# aq_mx_v1-6-0c.net
KiCad netlist of a schematic drawn in EAGLE
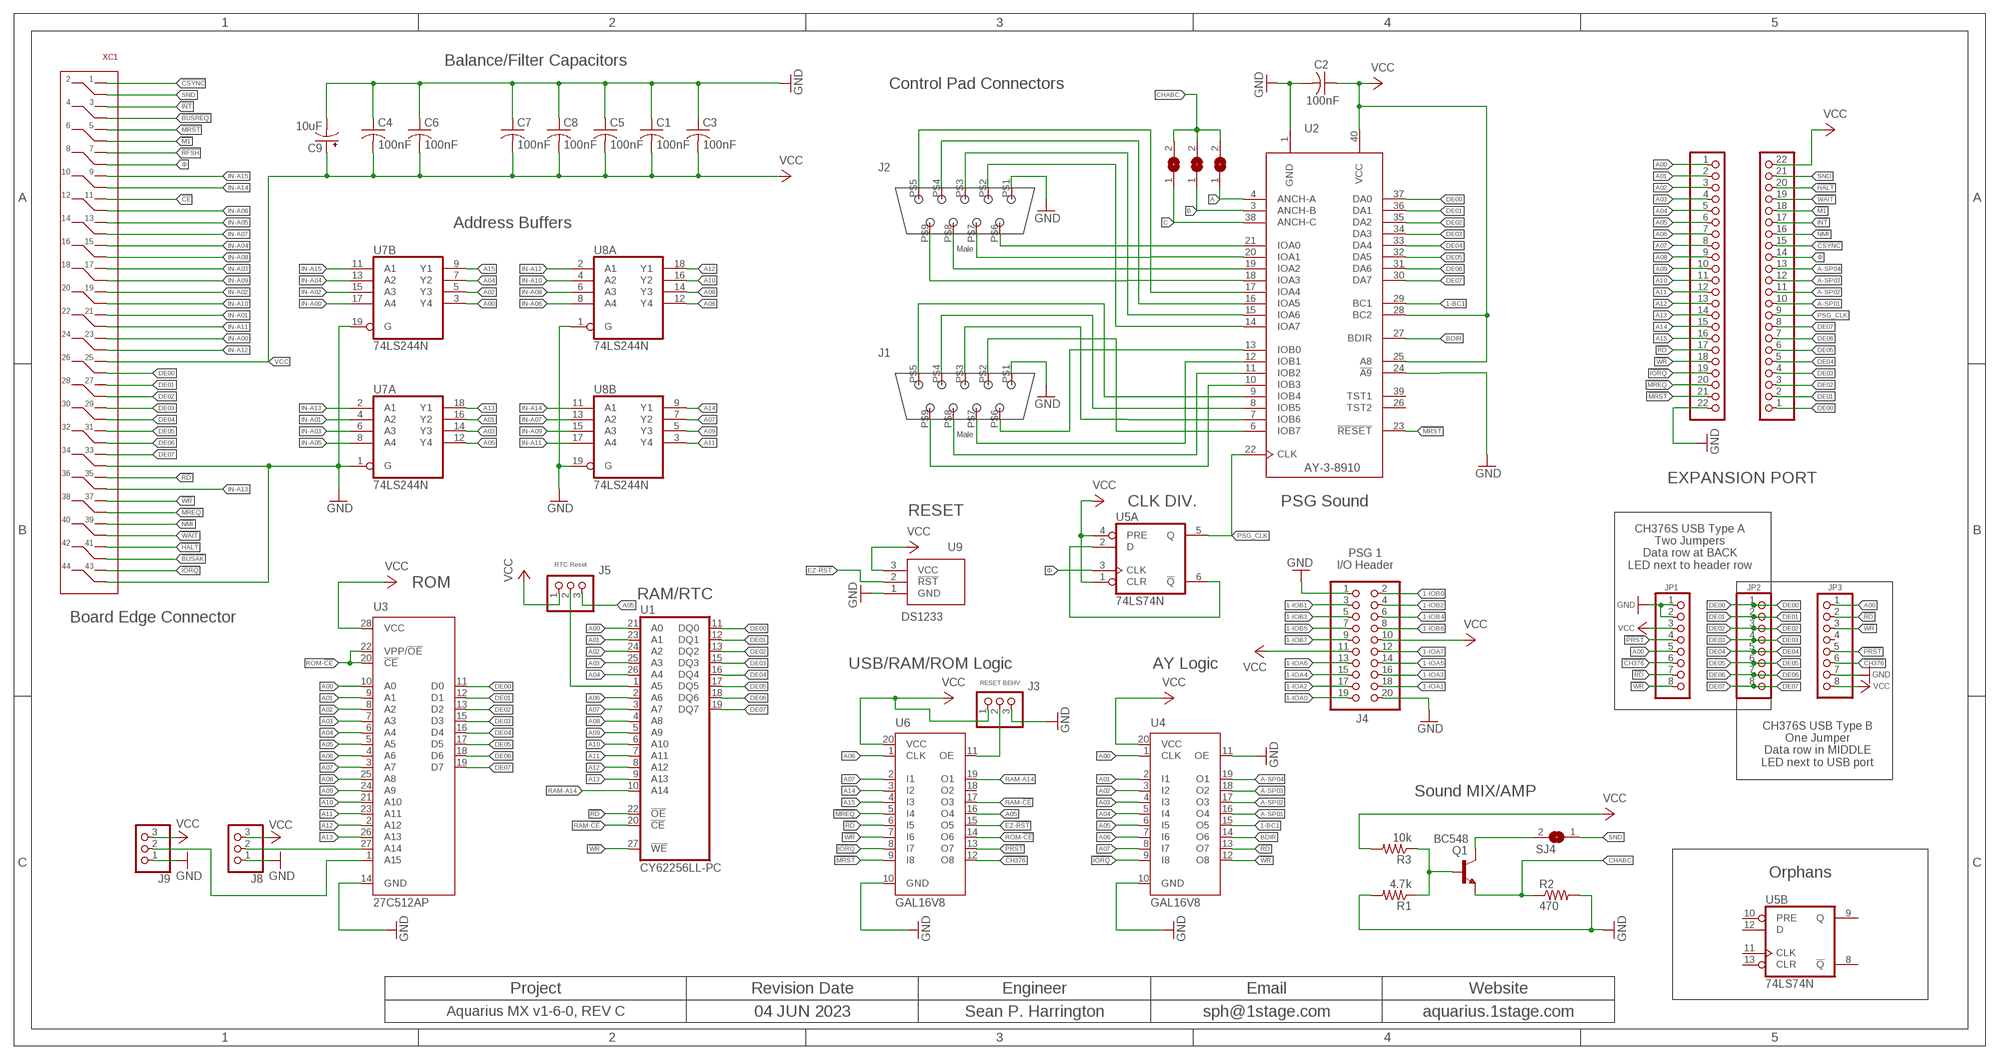
[diagram p0: schematic, sheet 1]

(export (version "E")
  (design (tool "Eeschema 10.0.6"))
  (components
    (comp (ref "C1")
      (value "100nF")
      (footprint "eagle-import:C050-025X075")
      (libsource (lib "eagle-import") (part "C-US050-025X075"))
    )
    (comp (ref "C2")
      (value "100nF")
      (footprint "eagle-import:C050-025X075")
      (libsource (lib "eagle-import") (part "C-US050-025X075"))
    )
    (comp (ref "C3")
      (value "100nF")
      (footprint "eagle-import:C050-025X075")
      (libsource (lib "eagle-import") (part "C-US050-025X075"))
    )
    (comp (ref "C4")
      (value "100nF")
      (footprint "eagle-import:C050-025X075")
      (libsource (lib "eagle-import") (part "C-US050-025X075"))
    )
    (comp (ref "C5")
      (value "100nF")
      (footprint "eagle-import:C050-025X075")
      (libsource (lib "eagle-import") (part "C-US050-025X075"))
    )
    (comp (ref "C6")
      (value "100nF")
      (footprint "eagle-import:C050-025X075")
      (libsource (lib "eagle-import") (part "C-US050-025X075"))
    )
    (comp (ref "C7")
      (value "100nF")
      (footprint "eagle-import:C050-025X075")
      (libsource (lib "eagle-import") (part "C-US050-025X075"))
    )
    (comp (ref "C8")
      (value "100nF")
      (footprint "eagle-import:C050-025X075")
      (libsource (lib "eagle-import") (part "C-US050-025X075"))
    )
    (comp (ref "C9")
      (value "10uF")
      (footprint "eagle-import:E22-6")
      (libsource (lib "eagle-import") (part "CPOL-USE22-6AXIAL"))
    )
    (comp (ref "J1")
      (value "DB9-MALE-RA")
      (footprint "eagle-import:DB9-MALE-RA")
      (libsource (lib "eagle-import") (part "DB9-MALE-RA"))
    )
    (comp (ref "J2")
      (value "DB9-MALE-RA")
      (footprint "eagle-import:DB9-MALE-RA")
      (libsource (lib "eagle-import") (part "DB9-MALE-RA"))
    )
    (comp (ref "J3")
      (value "RESET BEHV.")
      (footprint "eagle-import:1X03")
      (libsource (lib "eagle-import") (part "PINHD-1X3"))
    )
    (comp (ref "J4")
      (value "PINHD-2X10")
      (footprint "eagle-import:2X10")
      (libsource (lib "eagle-import") (part "PINHD-2X10"))
    )
    (comp (ref "J5")
      (value "RTC Reset")
      (footprint "eagle-import:1X03")
      (libsource (lib "eagle-import") (part "PINHD-1X3"))
    )
    (comp (ref "J6")
      (value "PINHD-1X22")
      (footprint "eagle-import:1X22")
      (libsource (lib "eagle-import") (part "PINHD-1X22"))
    )
    (comp (ref "J7")
      (value "PINHD-1X22")
      (footprint "eagle-import:1X22")
      (libsource (lib "eagle-import") (part "PINHD-1X22"))
    )
    (comp (ref "J8")
      (value "PINHD-1X3")
      (footprint "eagle-import:1X03")
      (libsource (lib "eagle-import") (part "PINHD-1X3"))
    )
    (comp (ref "J9")
      (value "PINHD-1X3")
      (footprint "eagle-import:1X03")
      (libsource (lib "eagle-import") (part "PINHD-1X3"))
    )
    (comp (ref "JP1")
      (value "PINHD-1X8")
      (footprint "eagle-import:1X08")
      (libsource (lib "eagle-import") (part "PINHD-1X8"))
    )
    (comp (ref "JP2")
      (value "PINHD-1X8")
      (footprint "eagle-import:1X08")
      (libsource (lib "eagle-import") (part "PINHD-1X8"))
    )
    (comp (ref "JP3")
      (value "PINHD-1X8")
      (footprint "eagle-import:1X08")
      (libsource (lib "eagle-import") (part "PINHD-1X8"))
    )
    (comp (ref "Q1")
      (value "BC548")
      (footprint "eagle-import:TO92-CBE")
      (libsource (lib "eagle-import") (part "-NPN-TO92-CBEBC548"))
    )
    (comp (ref "R1")
      (value "4.7k")
      (footprint "eagle-import:0204_7")
      (libsource (lib "eagle-import") (part "R-US_0204/7"))
    )
    (comp (ref "R2")
      (value "470")
      (footprint "eagle-import:0204_7")
      (libsource (lib "eagle-import") (part "R-US_0204/7"))
    )
    (comp (ref "R3")
      (value "10k")
      (footprint "eagle-import:0204_7")
      (libsource (lib "eagle-import") (part "R-US_0204/7"))
    )
    (comp (ref "SJ1") (value "SJ") (footprint "eagle-import:SJ") (libsource (lib "eagle-import") (part "SJ")))
    (comp (ref "SJ2") (value "SJ") (footprint "eagle-import:SJ") (libsource (lib "eagle-import") (part "SJ")))
    (comp (ref "SJ3") (value "SJ") (footprint "eagle-import:SJ") (libsource (lib "eagle-import") (part "SJ")))
    (comp (ref "SJ4") (value "SJ") (footprint "eagle-import:SJ") (libsource (lib "eagle-import") (part "SJ")))
    (comp (ref "U1")
      (value "CY62256LL-PC")
      (footprint "eagle-import:DIL28-6")
      (libsource (lib "eagle-import") (part "CY62256LL-?PC"))
    )
    (comp (ref "U2")
      (value "AY-3-8910")
      (footprint "eagle-import:RAD38910-DIL40-6")
      (libsource (lib "eagle-import") (part "RAD38910DIL40-6"))
    )
    (comp (ref "U3")
      (value "27C512AP")
      (footprint "eagle-import:DIL28-6")
      (fields (field (name "MPN") "M27C512-90B6"))
      (libsource (lib "eagle-import") (part "27512APC"))
    )
    (comp (ref "U4")
      (value "GAL16V8")
      (footprint "eagle-import:DIL20")
      (fields (field (name "MPN") "ATF16V8CZ-15PU"))
      (libsource (lib "eagle-import") (part "ATF16V8BP3"))
    )
    (comp (ref "U5")
      (value "74LS74N")
      (footprint "eagle-import:DIL14")
      (libsource (lib "eagle-import") (part "7474NLS"))
    )
    (comp (ref "U6")
      (value "GAL16V8")
      (footprint "eagle-import:DIL20")
      (fields (field (name "MPN") "ATF16V8CZ-15PU"))
      (libsource (lib "eagle-import") (part "ATF16V8BP3"))
    )
    (comp (ref "U7")
      (value "74LS244N")
      (footprint "eagle-import:DIL20")
      (libsource (lib "eagle-import") (part "74244NLS"))
    )
    (comp (ref "U8")
      (value "74LS244N")
      (footprint "eagle-import:DIL20")
      (libsource (lib "eagle-import") (part "74244NLS"))
    )
    (comp (ref "U9")
      (value "DS1233")
      (footprint "eagle-import:TO-92")
      (fields
        (field (name "ARROW_PART_NUMBER") "DS1233-10+")
        (field (name "MOUSER_PART_NUMBER") "700-DS1233-10")
      )
      (libsource (lib "eagle-import") (part "DS1233-10+"))
    )
    (comp (ref "XC1")
      (value "AQ-CART-EDGE")
      (footprint "eagle-import:AQ-CART-EDGE")
      (libsource (lib "eagle-import") (part "AQ-CART-EDGE"))
    )
  )
  (nets
    (net (code "1") (name "/EZ-~{RST}") (class "Default")
      (node (ref "U6") (pin "15") (pinfunction "O5_15") (pintype "output"))
      (node (ref "U9") (pin "2") (pinfunction "~{RST}_2") (pintype "input"))
    )
    (net (code "2") (name "/RAM-~{CE}") (class "Default")
      (node (ref "U1") (pin "20") (pinfunction "~{CE}_20") (pintype "input"))
      (node (ref "U6") (pin "17") (pinfunction "O3_17") (pintype "output"))
    )
    (net (code "3") (name "/ROM-~{CE}") (class "Default")
      (node (ref "U3") (pin "20") (pinfunction "~{CE}_20") (pintype "input"))
      (node (ref "U3") (pin "22") (pinfunction "VPP/~{OE}_22") (pintype "input"))
      (node (ref "U6") (pin "14") (pinfunction "O6_14") (pintype "output"))
    )
    (net (code "4") (name "/~{BUSAK}") (class "Default")
      (node (ref "XC1") (pin "P$42") (pinfunction "X42_P$42") (pintype "bidirectional"))
    )
    (net (code "5") (name "/~{BUSREQ}") (class "Default")
      (node (ref "XC1") (pin "P$4") (pinfunction "X4_P$4") (pintype "bidirectional"))
    )
    (net (code "6") (name "/~{CE}") (class "Default")
      (node (ref "XC1") (pin "P$11") (pinfunction "X11_P$11") (pintype "bidirectional"))
    )
    (net (code "7") (name "/~{CH376}") (class "Default")
      (node (ref "JP1") (pin "6") (pinfunction "6_6") (pintype "passive"))
      (node (ref "JP3") (pin "6") (pinfunction "6_6") (pintype "passive"))
      (node (ref "U6") (pin "12") (pinfunction "O8_12") (pintype "output"))
    )
    (net (code "8") (name "/~{CSYNC}") (class "Default")
      (node (ref "J6") (pin "15") (pinfunction "15_15") (pintype "passive"))
      (node (ref "XC1") (pin "P$1") (pinfunction "X1_P$1") (pintype "bidirectional"))
    )
    (net (code "9") (name "/~{HALT}") (class "Default")
      (node (ref "J6") (pin "20") (pinfunction "20_20") (pintype "passive"))
      (node (ref "XC1") (pin "P$41") (pinfunction "X41_P$41") (pintype "bidirectional"))
    )
    (net (code "10") (name "/~{INT}") (class "Default")
      (node (ref "J6") (pin "17") (pinfunction "17_17") (pintype "passive"))
      (node (ref "XC1") (pin "P$3") (pinfunction "X3_P$3") (pintype "bidirectional"))
    )
    (net (code "11") (name "/~{IORQ}") (class "Default")
      (node (ref "J7") (pin "19") (pinfunction "19_19") (pintype "passive"))
      (node (ref "U4") (pin "9") (pinfunction "I8_9") (pintype "input"))
      (node (ref "U6") (pin "8") (pinfunction "I7_8") (pintype "input"))
      (node (ref "XC1") (pin "P$43") (pinfunction "X43_P$43") (pintype "bidirectional"))
    )
    (net (code "12") (name "/~{M1}") (class "Default")
      (node (ref "J6") (pin "18") (pinfunction "18_18") (pintype "passive"))
      (node (ref "XC1") (pin "P$6") (pinfunction "X6_P$6") (pintype "bidirectional"))
    )
    (net (code "13") (name "/~{MREQ}") (class "Default")
      (node (ref "J7") (pin "20") (pinfunction "20_20") (pintype "passive"))
      (node (ref "U6") (pin "5") (pinfunction "I4_5") (pintype "input"))
      (node (ref "XC1") (pin "P$38") (pinfunction "X38_P$38") (pintype "bidirectional"))
    )
    (net (code "14") (name "/~{MRST}") (class "Default")
      (node (ref "J7") (pin "21") (pinfunction "21_21") (pintype "passive"))
      (node (ref "U2") (pin "23") (pinfunction "~{RESET}_23") (pintype "bidirectional"))
      (node (ref "U6") (pin "9") (pinfunction "I8_9") (pintype "input"))
      (node (ref "XC1") (pin "P$5") (pinfunction "X5_P$5") (pintype "bidirectional"))
    )
    (net (code "15") (name "/~{NMI}") (class "Default")
      (node (ref "J6") (pin "16") (pinfunction "16_16") (pintype "passive"))
      (node (ref "XC1") (pin "P$39") (pinfunction "X39_P$39") (pintype "bidirectional"))
    )
    (net (code "16") (name "/~{PRST}") (class "Default")
      (node (ref "JP1") (pin "4") (pinfunction "4_4") (pintype "passive"))
      (node (ref "JP3") (pin "5") (pinfunction "5_5") (pintype "passive"))
      (node (ref "U6") (pin "13") (pinfunction "O7_13") (pintype "output"))
    )
    (net (code "17") (name "/~{RD}") (class "Default")
      (node (ref "J7") (pin "17") (pinfunction "17_17") (pintype "passive"))
      (node (ref "JP1") (pin "7") (pinfunction "7_7") (pintype "passive"))
      (node (ref "JP3") (pin "2") (pinfunction "2_2") (pintype "passive"))
      (node (ref "U1") (pin "22") (pinfunction "~{OE}_22") (pintype "input"))
      (node (ref "U4") (pin "13") (pinfunction "O7_13") (pintype "output"))
      (node (ref "U6") (pin "6") (pinfunction "I5_6") (pintype "input"))
      (node (ref "XC1") (pin "P$35") (pinfunction "X35_P$35") (pintype "bidirectional"))
    )
    (net (code "18") (name "/~{RFSH}") (class "Default")
      (node (ref "XC1") (pin "P$7") (pinfunction "X7_P$7") (pintype "bidirectional"))
    )
    (net (code "19") (name "/~{WAIT}") (class "Default")
      (node (ref "J6") (pin "19") (pinfunction "19_19") (pintype "passive"))
      (node (ref "XC1") (pin "P$40") (pinfunction "X40_P$40") (pintype "bidirectional"))
    )
    (net (code "20") (name "/~{WR}") (class "Default")
      (node (ref "J7") (pin "18") (pinfunction "18_18") (pintype "passive"))
      (node (ref "JP1") (pin "8") (pinfunction "8_8") (pintype "passive"))
      (node (ref "JP3") (pin "3") (pinfunction "3_3") (pintype "passive"))
      (node (ref "U1") (pin "27") (pinfunction "~{WE}_27") (pintype "input"))
      (node (ref "U4") (pin "12") (pinfunction "O8_12") (pintype "output"))
      (node (ref "U6") (pin "7") (pinfunction "I6_7") (pintype "input"))
      (node (ref "XC1") (pin "P$37") (pinfunction "X37_P$37") (pintype "bidirectional"))
    )
    (net (code "21") (name "1-BC1") (class "Default")
      (node (ref "U2") (pin "29") (pinfunction "BC1_29") (pintype "bidirectional"))
      (node (ref "U4") (pin "15") (pinfunction "O5_15") (pintype "output"))
    )
    (net (code "22") (name "1-IOA0") (class "Default")
      (node (ref "J2") (pin "P$6") (pinfunction "P$6_P$6") (pintype "bidirectional"))
      (node (ref "J4") (pin "19") (pinfunction "19_19") (pintype "passive"))
      (node (ref "U2") (pin "21") (pinfunction "IOA0_21") (pintype "bidirectional"))
    )
    (net (code "23") (name "1-IOA1") (class "Default")
      (node (ref "J2") (pin "P$7") (pinfunction "P$7_P$7") (pintype "bidirectional"))
      (node (ref "J4") (pin "18") (pinfunction "18_18") (pintype "passive"))
      (node (ref "U2") (pin "20") (pinfunction "IOA1_20") (pintype "bidirectional"))
    )
    (net (code "24") (name "1-IOA2") (class "Default")
      (node (ref "J2") (pin "P$8") (pinfunction "P$8_P$8") (pintype "bidirectional"))
      (node (ref "J4") (pin "17") (pinfunction "17_17") (pintype "passive"))
      (node (ref "U2") (pin "19") (pinfunction "IOA2_19") (pintype "bidirectional"))
    )
    (net (code "25") (name "1-IOA3") (class "Default")
      (node (ref "J2") (pin "P$9") (pinfunction "P$9_P$9") (pintype "bidirectional"))
      (node (ref "J4") (pin "16") (pinfunction "16_16") (pintype "passive"))
      (node (ref "U2") (pin "18") (pinfunction "IOA3_18") (pintype "bidirectional"))
    )
    (net (code "26") (name "1-IOA4") (class "Default")
      (node (ref "J2") (pin "P$5") (pinfunction "P$5_P$5") (pintype "bidirectional"))
      (node (ref "J4") (pin "15") (pinfunction "15_15") (pintype "passive"))
      (node (ref "U2") (pin "17") (pinfunction "IOA4_17") (pintype "bidirectional"))
    )
    (net (code "27") (name "1-IOA5") (class "Default")
      (node (ref "J2") (pin "P$4") (pinfunction "P$4_P$4") (pintype "bidirectional"))
      (node (ref "J4") (pin "14") (pinfunction "14_14") (pintype "passive"))
      (node (ref "U2") (pin "16") (pinfunction "IOA5_16") (pintype "bidirectional"))
    )
    (net (code "28") (name "1-IOA6") (class "Default")
      (node (ref "J2") (pin "P$3") (pinfunction "P$3_P$3") (pintype "bidirectional"))
      (node (ref "J4") (pin "13") (pinfunction "13_13") (pintype "passive"))
      (node (ref "U2") (pin "15") (pinfunction "IOA6_15") (pintype "bidirectional"))
    )
    (net (code "29") (name "1-IOA7") (class "Default")
      (node (ref "J2") (pin "P$2") (pinfunction "P$2_P$2") (pintype "bidirectional"))
      (node (ref "J4") (pin "12") (pinfunction "12_12") (pintype "passive"))
      (node (ref "U2") (pin "14") (pinfunction "IOA7_14") (pintype "bidirectional"))
    )
    (net (code "30") (name "1-IOB0") (class "Default")
      (node (ref "J1") (pin "P$6") (pinfunction "P$6_P$6") (pintype "bidirectional"))
      (node (ref "J4") (pin "2") (pinfunction "2_2") (pintype "passive"))
      (node (ref "U2") (pin "13") (pinfunction "IOB0_13") (pintype "bidirectional"))
    )
    (net (code "31") (name "1-IOB1") (class "Default")
      (node (ref "J1") (pin "P$7") (pinfunction "P$7_P$7") (pintype "bidirectional"))
      (node (ref "J4") (pin "3") (pinfunction "3_3") (pintype "passive"))
      (node (ref "U2") (pin "12") (pinfunction "IOB1_12") (pintype "bidirectional"))
    )
    (net (code "32") (name "1-IOB2") (class "Default")
      (node (ref "J1") (pin "P$8") (pinfunction "P$8_P$8") (pintype "bidirectional"))
      (node (ref "J4") (pin "4") (pinfunction "4_4") (pintype "passive"))
      (node (ref "U2") (pin "11") (pinfunction "IOB2_11") (pintype "bidirectional"))
    )
    (net (code "33") (name "1-IOB3") (class "Default")
      (node (ref "J1") (pin "P$9") (pinfunction "P$9_P$9") (pintype "bidirectional"))
      (node (ref "J4") (pin "5") (pinfunction "5_5") (pintype "passive"))
      (node (ref "U2") (pin "10") (pinfunction "IOB3_10") (pintype "bidirectional"))
    )
    (net (code "34") (name "1-IOB4") (class "Default")
      (node (ref "J1") (pin "P$5") (pinfunction "P$5_P$5") (pintype "bidirectional"))
      (node (ref "J4") (pin "6") (pinfunction "6_6") (pintype "passive"))
      (node (ref "U2") (pin "9") (pinfunction "IOB4_9") (pintype "bidirectional"))
    )
    (net (code "35") (name "1-IOB5") (class "Default")
      (node (ref "J1") (pin "P$4") (pinfunction "P$4_P$4") (pintype "bidirectional"))
      (node (ref "J4") (pin "7") (pinfunction "7_7") (pintype "passive"))
      (node (ref "U2") (pin "8") (pinfunction "IOB5_8") (pintype "bidirectional"))
    )
    (net (code "36") (name "1-IOB6") (class "Default")
      (node (ref "J1") (pin "P$3") (pinfunction "P$3_P$3") (pintype "bidirectional"))
      (node (ref "J4") (pin "8") (pinfunction "8_8") (pintype "passive"))
      (node (ref "U2") (pin "7") (pinfunction "IOB6_7") (pintype "bidirectional"))
    )
    (net (code "37") (name "1-IOB7") (class "Default")
      (node (ref "J1") (pin "P$2") (pinfunction "P$2_P$2") (pintype "bidirectional"))
      (node (ref "J4") (pin "9") (pinfunction "9_9") (pintype "passive"))
      (node (ref "U2") (pin "6") (pinfunction "IOB7_6") (pintype "bidirectional"))
    )
    (net (code "38") (name "A") (class "Default")
      (node (ref "SJ1") (pin "1") (pinfunction "1_1") (pintype "passive"))
      (node (ref "U2") (pin "4") (pinfunction "ANCH-A_4") (pintype "bidirectional"))
    )
    (net (code "39") (name "A-SP01") (class "Default")
      (node (ref "J6") (pin "10") (pinfunction "10_10") (pintype "passive"))
      (node (ref "U4") (pin "16") (pinfunction "O4_16") (pintype "output"))
    )
    (net (code "40") (name "A-SP02") (class "Default")
      (node (ref "J6") (pin "11") (pinfunction "11_11") (pintype "passive"))
      (node (ref "U4") (pin "17") (pinfunction "O3_17") (pintype "output"))
    )
    (net (code "41") (name "A-SP03") (class "Default")
      (node (ref "J6") (pin "12") (pinfunction "12_12") (pintype "passive"))
      (node (ref "U4") (pin "18") (pinfunction "O2_18") (pintype "output"))
    )
    (net (code "42") (name "A-SP04") (class "Default")
      (node (ref "J6") (pin "13") (pinfunction "13_13") (pintype "passive"))
      (node (ref "U4") (pin "19") (pinfunction "O1_19") (pintype "output"))
    )
    (net (code "43") (name "A00") (class "Default")
      (node (ref "J7") (pin "1") (pinfunction "1_1") (pintype "passive"))
      (node (ref "JP1") (pin "5") (pinfunction "5_5") (pintype "passive"))
      (node (ref "JP3") (pin "1") (pinfunction "1_1") (pintype "passive"))
      (node (ref "U1") (pin "21") (pinfunction "A0_21") (pintype "input"))
      (node (ref "U3") (pin "10") (pinfunction "A0_10") (pintype "input"))
      (node (ref "U4") (pin "1") (pinfunction "CLK_1") (pintype "input"))
      (node (ref "U7") (pin "3") (pinfunction "Y4_3") (pintype "tri_state"))
    )
    (net (code "44") (name "A01") (class "Default")
      (node (ref "J7") (pin "2") (pinfunction "2_2") (pintype "passive"))
      (node (ref "U1") (pin "23") (pinfunction "A1_23") (pintype "input"))
      (node (ref "U3") (pin "9") (pinfunction "A1_9") (pintype "input"))
      (node (ref "U4") (pin "2") (pinfunction "I1_2") (pintype "input"))
      (node (ref "U7") (pin "16") (pinfunction "Y2_16") (pintype "tri_state"))
    )
    (net (code "45") (name "A02") (class "Default")
      (node (ref "J7") (pin "3") (pinfunction "3_3") (pintype "passive"))
      (node (ref "U1") (pin "24") (pinfunction "A2_24") (pintype "input"))
      (node (ref "U3") (pin "8") (pinfunction "A2_8") (pintype "input"))
      (node (ref "U4") (pin "3") (pinfunction "I2_3") (pintype "input"))
      (node (ref "U7") (pin "5") (pinfunction "Y3_5") (pintype "tri_state"))
    )
    (net (code "46") (name "A03") (class "Default")
      (node (ref "J7") (pin "4") (pinfunction "4_4") (pintype "passive"))
      (node (ref "U1") (pin "25") (pinfunction "A3_25") (pintype "input"))
      (node (ref "U3") (pin "7") (pinfunction "A3_7") (pintype "input"))
      (node (ref "U4") (pin "4") (pinfunction "I3_4") (pintype "input"))
      (node (ref "U7") (pin "14") (pinfunction "Y3_14") (pintype "tri_state"))
    )
    (net (code "47") (name "A04") (class "Default")
      (node (ref "J7") (pin "5") (pinfunction "5_5") (pintype "passive"))
      (node (ref "U1") (pin "26") (pinfunction "A4_26") (pintype "input"))
      (node (ref "U3") (pin "6") (pinfunction "A4_6") (pintype "input"))
      (node (ref "U4") (pin "5") (pinfunction "I4_5") (pintype "input"))
      (node (ref "U7") (pin "7") (pinfunction "Y2_7") (pintype "tri_state"))
    )
    (net (code "48") (name "A05") (class "Default")
      (node (ref "J5") (pin "3") (pinfunction "3_3") (pintype "passive"))
      (node (ref "J7") (pin "6") (pinfunction "6_6") (pintype "passive"))
      (node (ref "U3") (pin "5") (pinfunction "A5_5") (pintype "input"))
      (node (ref "U4") (pin "6") (pinfunction "I5_6") (pintype "input"))
      (node (ref "U6") (pin "16") (pinfunction "O4_16") (pintype "output"))
      (node (ref "U7") (pin "12") (pinfunction "Y4_12") (pintype "tri_state"))
    )
    (net (code "49") (name "A06") (class "Default")
      (node (ref "J7") (pin "7") (pinfunction "7_7") (pintype "passive"))
      (node (ref "U1") (pin "2") (pinfunction "A6_2") (pintype "input"))
      (node (ref "U3") (pin "4") (pinfunction "A6_4") (pintype "input"))
      (node (ref "U4") (pin "7") (pinfunction "I6_7") (pintype "input"))
      (node (ref "U6") (pin "1") (pinfunction "CLK_1") (pintype "input"))
      (node (ref "U8") (pin "12") (pinfunction "Y4_12") (pintype "tri_state"))
    )
    (net (code "50") (name "A07") (class "Default")
      (node (ref "J7") (pin "8") (pinfunction "8_8") (pintype "passive"))
      (node (ref "U1") (pin "3") (pinfunction "A7_3") (pintype "input"))
      (node (ref "U3") (pin "3") (pinfunction "A7_3") (pintype "input"))
      (node (ref "U4") (pin "8") (pinfunction "I7_8") (pintype "input"))
      (node (ref "U6") (pin "2") (pinfunction "I1_2") (pintype "input"))
      (node (ref "U8") (pin "7") (pinfunction "Y2_7") (pintype "tri_state"))
    )
    (net (code "51") (name "A08") (class "Default")
      (node (ref "J7") (pin "9") (pinfunction "9_9") (pintype "passive"))
      (node (ref "U1") (pin "4") (pinfunction "A8_4") (pintype "input"))
      (node (ref "U3") (pin "25") (pinfunction "A8_25") (pintype "input"))
      (node (ref "U8") (pin "14") (pinfunction "Y3_14") (pintype "tri_state"))
    )
    (net (code "52") (name "A09") (class "Default")
      (node (ref "J7") (pin "10") (pinfunction "10_10") (pintype "passive"))
      (node (ref "U1") (pin "5") (pinfunction "A9_5") (pintype "input"))
      (node (ref "U3") (pin "24") (pinfunction "A9_24") (pintype "input"))
      (node (ref "U8") (pin "5") (pinfunction "Y3_5") (pintype "tri_state"))
    )
    (net (code "53") (name "A10") (class "Default")
      (node (ref "J7") (pin "11") (pinfunction "11_11") (pintype "passive"))
      (node (ref "U1") (pin "6") (pinfunction "A10_6") (pintype "input"))
      (node (ref "U3") (pin "21") (pinfunction "A10_21") (pintype "input"))
      (node (ref "U8") (pin "16") (pinfunction "Y2_16") (pintype "tri_state"))
    )
    (net (code "54") (name "A11") (class "Default")
      (node (ref "J7") (pin "12") (pinfunction "12_12") (pintype "passive"))
      (node (ref "U1") (pin "7") (pinfunction "A11_7") (pintype "input"))
      (node (ref "U3") (pin "23") (pinfunction "A11_23") (pintype "input"))
      (node (ref "U8") (pin "3") (pinfunction "Y4_3") (pintype "tri_state"))
    )
    (net (code "55") (name "A12") (class "Default")
      (node (ref "J7") (pin "13") (pinfunction "13_13") (pintype "passive"))
      (node (ref "U1") (pin "8") (pinfunction "A12_8") (pintype "input"))
      (node (ref "U3") (pin "2") (pinfunction "A12_2") (pintype "input"))
      (node (ref "U8") (pin "18") (pinfunction "Y1_18") (pintype "tri_state"))
    )
    (net (code "56") (name "A13") (class "Default")
      (node (ref "J7") (pin "14") (pinfunction "14_14") (pintype "passive"))
      (node (ref "U1") (pin "9") (pinfunction "A13_9") (pintype "input"))
      (node (ref "U3") (pin "26") (pinfunction "A13_26") (pintype "input"))
      (node (ref "U7") (pin "18") (pinfunction "Y1_18") (pintype "tri_state"))
    )
    (net (code "57") (name "A14") (class "Default")
      (node (ref "J7") (pin "15") (pinfunction "15_15") (pintype "passive"))
      (node (ref "U6") (pin "3") (pinfunction "I2_3") (pintype "input"))
      (node (ref "U8") (pin "9") (pinfunction "Y1_9") (pintype "tri_state"))
    )
    (net (code "58") (name "A15") (class "Default")
      (node (ref "J7") (pin "16") (pinfunction "16_16") (pintype "passive"))
      (node (ref "U6") (pin "4") (pinfunction "I3_4") (pintype "input"))
      (node (ref "U7") (pin "9") (pinfunction "Y1_9") (pintype "tri_state"))
    )
    (net (code "59") (name "B") (class "Default")
      (node (ref "SJ2") (pin "1") (pinfunction "1_1") (pintype "passive"))
      (node (ref "U2") (pin "3") (pinfunction "ANCH-B_3") (pintype "bidirectional"))
    )
    (net (code "60") (name "BDIR") (class "Default")
      (node (ref "U2") (pin "27") (pinfunction "BDIR_27") (pintype "bidirectional"))
      (node (ref "U4") (pin "14") (pinfunction "O6_14") (pintype "output"))
    )
    (net (code "61") (name "C") (class "Default")
      (node (ref "SJ3") (pin "1") (pinfunction "1_1") (pintype "passive"))
      (node (ref "U2") (pin "38") (pinfunction "ANCH-C_38") (pintype "bidirectional"))
    )
    (net (code "62") (name "CHABC") (class "Default")
      (node (ref "Q1") (pin "E") (pinfunction "E_E") (pintype "passive"))
      (node (ref "R2") (pin "1") (pinfunction "1_1") (pintype "passive"))
      (node (ref "SJ1") (pin "2") (pinfunction "2_2") (pintype "passive"))
      (node (ref "SJ2") (pin "2") (pinfunction "2_2") (pintype "passive"))
      (node (ref "SJ3") (pin "2") (pinfunction "2_2") (pintype "passive"))
    )
    (net (code "63") (name "DE00") (class "Default")
      (node (ref "J6") (pin "1") (pinfunction "1_1") (pintype "passive"))
      (node (ref "JP2") (pin "1") (pinfunction "1_1") (pintype "passive"))
      (node (ref "U1") (pin "11") (pinfunction "DQ0_11") (pintype "bidirectional"))
      (node (ref "U2") (pin "37") (pinfunction "DA0_37") (pintype "bidirectional"))
      (node (ref "U3") (pin "11") (pinfunction "D0_11") (pintype "tri_state"))
      (node (ref "XC1") (pin "P$26") (pinfunction "X26_P$26") (pintype "bidirectional"))
    )
    (net (code "64") (name "DE01") (class "Default")
      (node (ref "J6") (pin "2") (pinfunction "2_2") (pintype "passive"))
      (node (ref "JP2") (pin "2") (pinfunction "2_2") (pintype "passive"))
      (node (ref "U1") (pin "12") (pinfunction "DQ1_12") (pintype "bidirectional"))
      (node (ref "U2") (pin "36") (pinfunction "DA1_36") (pintype "bidirectional"))
      (node (ref "U3") (pin "12") (pinfunction "D1_12") (pintype "tri_state"))
      (node (ref "XC1") (pin "P$27") (pinfunction "X27_P$27") (pintype "bidirectional"))
    )
    (net (code "65") (name "DE02") (class "Default")
      (node (ref "J6") (pin "3") (pinfunction "3_3") (pintype "passive"))
      (node (ref "JP2") (pin "3") (pinfunction "3_3") (pintype "passive"))
      (node (ref "U1") (pin "13") (pinfunction "DQ2_13") (pintype "bidirectional"))
      (node (ref "U2") (pin "35") (pinfunction "DA2_35") (pintype "bidirectional"))
      (node (ref "U3") (pin "13") (pinfunction "D2_13") (pintype "tri_state"))
      (node (ref "XC1") (pin "P$28") (pinfunction "X28_P$28") (pintype "bidirectional"))
    )
    (net (code "66") (name "DE03") (class "Default")
      (node (ref "J6") (pin "4") (pinfunction "4_4") (pintype "passive"))
      (node (ref "JP2") (pin "4") (pinfunction "4_4") (pintype "passive"))
      (node (ref "U1") (pin "15") (pinfunction "DQ3_15") (pintype "bidirectional"))
      (node (ref "U2") (pin "34") (pinfunction "DA3_34") (pintype "bidirectional"))
      (node (ref "U3") (pin "15") (pinfunction "D3_15") (pintype "tri_state"))
      (node (ref "XC1") (pin "P$29") (pinfunction "X29_P$29") (pintype "bidirectional"))
    )
    (net (code "67") (name "DE04") (class "Default")
      (node (ref "J6") (pin "5") (pinfunction "5_5") (pintype "passive"))
      (node (ref "JP2") (pin "5") (pinfunction "5_5") (pintype "passive"))
      (node (ref "U1") (pin "16") (pinfunction "DQ4_16") (pintype "bidirectional"))
      (node (ref "U2") (pin "33") (pinfunction "DA4_33") (pintype "bidirectional"))
      (node (ref "U3") (pin "16") (pinfunction "D4_16") (pintype "tri_state"))
      (node (ref "XC1") (pin "P$30") (pinfunction "X30_P$30") (pintype "bidirectional"))
    )
    (net (code "68") (name "DE05") (class "Default")
      (node (ref "J6") (pin "6") (pinfunction "6_6") (pintype "passive"))
      (node (ref "JP2") (pin "6") (pinfunction "6_6") (pintype "passive"))
      (node (ref "U1") (pin "17") (pinfunction "DQ5_17") (pintype "bidirectional"))
      (node (ref "U2") (pin "32") (pinfunction "DA5_32") (pintype "bidirectional"))
      (node (ref "U3") (pin "17") (pinfunction "D5_17") (pintype "tri_state"))
      (node (ref "XC1") (pin "P$31") (pinfunction "X31_P$31") (pintype "bidirectional"))
    )
    (net (code "69") (name "DE06") (class "Default")
      (node (ref "J6") (pin "7") (pinfunction "7_7") (pintype "passive"))
      (node (ref "JP2") (pin "7") (pinfunction "7_7") (pintype "passive"))
      (node (ref "U1") (pin "18") (pinfunction "DQ6_18") (pintype "bidirectional"))
      (node (ref "U2") (pin "31") (pinfunction "DA6_31") (pintype "bidirectional"))
      (node (ref "U3") (pin "18") (pinfunction "D6_18") (pintype "tri_state"))
      (node (ref "XC1") (pin "P$32") (pinfunction "X32_P$32") (pintype "bidirectional"))
    )
    (net (code "70") (name "DE07") (class "Default")
      (node (ref "J6") (pin "8") (pinfunction "8_8") (pintype "passive"))
      (node (ref "JP2") (pin "8") (pinfunction "8_8") (pintype "passive"))
      (node (ref "U1") (pin "19") (pinfunction "DQ7_19") (pintype "bidirectional"))
      (node (ref "U2") (pin "30") (pinfunction "DA7_30") (pintype "bidirectional"))
      (node (ref "U3") (pin "19") (pinfunction "D7_19") (pintype "tri_state"))
      (node (ref "XC1") (pin "P$33") (pinfunction "X33_P$33") (pintype "bidirectional"))
    )
    (net (code "71") (name "GND") (class "Default")
      (node (ref "C1") (pin "1") (pinfunction "1_1") (pintype "passive"))
      (node (ref "C2") (pin "2") (pinfunction "2_2") (pintype "passive"))
      (node (ref "C3") (pin "1") (pinfunction "1_1") (pintype "passive"))
      (node (ref "C4") (pin "1") (pinfunction "1_1") (pintype "passive"))
      (node (ref "C5") (pin "1") (pinfunction "1_1") (pintype "passive"))
      (node (ref "C6") (pin "1") (pinfunction "1_1") (pintype "passive"))
      (node (ref "C7") (pin "1") (pinfunction "1_1") (pintype "passive"))
      (node (ref "C8") (pin "1") (pinfunction "1_1") (pintype "passive"))
      (node (ref "C9") (pin "-") (pinfunction "-_-") (pintype "passive"))
      (node (ref "J1") (pin "P$1") (pinfunction "P$1_P$1") (pintype "bidirectional"))
      (node (ref "J2") (pin "P$1") (pinfunction "P$1_P$1") (pintype "bidirectional"))
      (node (ref "J3") (pin "3") (pinfunction "3_3") (pintype "passive"))
      (node (ref "J4") (pin "1") (pinfunction "1_1") (pintype "passive"))
      (node (ref "J4") (pin "20") (pinfunction "20_20") (pintype "passive"))
      (node (ref "J7") (pin "22") (pinfunction "22_22") (pintype "passive"))
      (node (ref "J8") (pin "1") (pinfunction "1_1") (pintype "passive"))
      (node (ref "J9") (pin "1") (pinfunction "1_1") (pintype "passive"))
      (node (ref "JP1") (pin "1") (pinfunction "1_1") (pintype "passive"))
      (node (ref "JP1") (pin "2") (pinfunction "2_2") (pintype "passive"))
      (node (ref "JP3") (pin "7") (pinfunction "7_7") (pintype "passive"))
      (node (ref "R1") (pin "2") (pinfunction "2_2") (pintype "passive"))
      (node (ref "R2") (pin "2") (pinfunction "2_2") (pintype "passive"))
      (node (ref "U2") (pin "1") (pinfunction "GND_1") (pintype "power_in"))
      (node (ref "U2") (pin "24") (pinfunction "~{A9}_24") (pintype "bidirectional"))
      (node (ref "U3") (pin "14") (pinfunction "GND_14") (pintype "power_in"))
      (node (ref "U4") (pin "10") (pinfunction "GND_10") (pintype "power_in"))
      (node (ref "U4") (pin "11") (pinfunction "OE_11") (pintype "input"))
      (node (ref "U6") (pin "10") (pinfunction "GND_10") (pintype "power_in"))
      (node (ref "U7") (pin "1") (pinfunction "G_1") (pintype "input"))
      (node (ref "U7") (pin "19") (pinfunction "G_19") (pintype "input"))
      (node (ref "U8") (pin "1") (pinfunction "G_1") (pintype "input"))
      (node (ref "U8") (pin "19") (pinfunction "G_19") (pintype "input"))
      (node (ref "U9") (pin "1") (pinfunction "GND_1") (pintype "power_in"))
      (node (ref "XC1") (pin "P$34") (pinfunction "X34_P$34") (pintype "bidirectional"))
      (node (ref "XC1") (pin "P$44") (pinfunction "X44_P$44") (pintype "bidirectional"))
    )
    (net (code "72") (name "IN-A00") (class "Default")
      (node (ref "U7") (pin "17") (pinfunction "A4_17") (pintype "input"))
      (node (ref "XC1") (pin "P$23") (pinfunction "X23_P$23") (pintype "bidirectional"))
    )
    (net (code "73") (name "IN-A01") (class "Default")
      (node (ref "U7") (pin "4") (pinfunction "A2_4") (pintype "input"))
      (node (ref "XC1") (pin "P$21") (pinfunction "X21_P$21") (pintype "bidirectional"))
    )
    (net (code "74") (name "IN-A02") (class "Default")
      (node (ref "U7") (pin "15") (pinfunction "A3_15") (pintype "input"))
      (node (ref "XC1") (pin "P$19") (pinfunction "X19_P$19") (pintype "bidirectional"))
    )
    (net (code "75") (name "IN-A03") (class "Default")
      (node (ref "U7") (pin "6") (pinfunction "A3_6") (pintype "input"))
      (node (ref "XC1") (pin "P$17") (pinfunction "X17_P$17") (pintype "bidirectional"))
    )
    (net (code "76") (name "IN-A04") (class "Default")
      (node (ref "U7") (pin "13") (pinfunction "A2_13") (pintype "input"))
      (node (ref "XC1") (pin "P$15") (pinfunction "X15_P$15") (pintype "bidirectional"))
    )
    (net (code "77") (name "IN-A05") (class "Default")
      (node (ref "U7") (pin "8") (pinfunction "A4_8") (pintype "input"))
      (node (ref "XC1") (pin "P$13") (pinfunction "X13_P$13") (pintype "bidirectional"))
    )
    (net (code "78") (name "IN-A06") (class "Default")
      (node (ref "U8") (pin "8") (pinfunction "A4_8") (pintype "input"))
      (node (ref "XC1") (pin "P$12") (pinfunction "X12_P$12") (pintype "bidirectional"))
    )
    (net (code "79") (name "IN-A07") (class "Default")
      (node (ref "U8") (pin "13") (pinfunction "A2_13") (pintype "input"))
      (node (ref "XC1") (pin "P$14") (pinfunction "X14_P$14") (pintype "bidirectional"))
    )
    (net (code "80") (name "IN-A08") (class "Default")
      (node (ref "U8") (pin "6") (pinfunction "A3_6") (pintype "input"))
      (node (ref "XC1") (pin "P$16") (pinfunction "X16_P$16") (pintype "bidirectional"))
    )
    (net (code "81") (name "IN-A09") (class "Default")
      (node (ref "U8") (pin "15") (pinfunction "A3_15") (pintype "input"))
      (node (ref "XC1") (pin "P$18") (pinfunction "X18_P$18") (pintype "bidirectional"))
    )
    (net (code "82") (name "IN-A10") (class "Default")
      (node (ref "U8") (pin "4") (pinfunction "A2_4") (pintype "input"))
      (node (ref "XC1") (pin "P$20") (pinfunction "X20_P$20") (pintype "bidirectional"))
    )
    (net (code "83") (name "IN-A11") (class "Default")
      (node (ref "U8") (pin "17") (pinfunction "A4_17") (pintype "input"))
      (node (ref "XC1") (pin "P$22") (pinfunction "X22_P$22") (pintype "bidirectional"))
    )
    (net (code "84") (name "IN-A12") (class "Default")
      (node (ref "U8") (pin "2") (pinfunction "A1_2") (pintype "input"))
      (node (ref "XC1") (pin "P$24") (pinfunction "X24_P$24") (pintype "bidirectional"))
    )
    (net (code "85") (name "IN-A13") (class "Default")
      (node (ref "U7") (pin "2") (pinfunction "A1_2") (pintype "input"))
      (node (ref "XC1") (pin "P$36") (pinfunction "X36_P$36") (pintype "bidirectional"))
    )
    (net (code "86") (name "IN-A14") (class "Default")
      (node (ref "U8") (pin "11") (pinfunction "A1_11") (pintype "input"))
      (node (ref "XC1") (pin "P$10") (pinfunction "X10_P$10") (pintype "bidirectional"))
    )
    (net (code "87") (name "IN-A15") (class "Default")
      (node (ref "U7") (pin "11") (pinfunction "A1_11") (pintype "input"))
      (node (ref "XC1") (pin "P$9") (pinfunction "X9_P$9") (pintype "bidirectional"))
    )
    (net (code "88") (name "Net-(Q1-PadB)") (class "Default")
      (node (ref "Q1") (pin "B") (pinfunction "B_B") (pintype "passive"))
      (node (ref "R1") (pin "1") (pinfunction "1_1") (pintype "passive"))
      (node (ref "R3") (pin "1") (pinfunction "1_1") (pintype "passive"))
    )
    (net (code "89") (name "Net-(Q1-PadC)") (class "Default")
      (node (ref "Q1") (pin "C") (pinfunction "C_C") (pintype "passive"))
      (node (ref "SJ4") (pin "2") (pinfunction "2_2") (pintype "passive"))
    )
    (net (code "90") (name "Net-(U1A-A5)") (class "Default")
      (node (ref "J5") (pin "2") (pinfunction "2_2") (pintype "passive"))
      (node (ref "U1") (pin "1") (pinfunction "A5_1") (pintype "input"))
    )
    (net (code "91") (name "Net-(U3-A14)") (class "Default")
      (node (ref "J8") (pin "2") (pinfunction "2_2") (pintype "passive"))
      (node (ref "U3") (pin "27") (pinfunction "A14_27") (pintype "input"))
    )
    (net (code "92") (name "Net-(U3-A15)") (class "Default")
      (node (ref "J9") (pin "2") (pinfunction "2_2") (pintype "passive"))
      (node (ref "U3") (pin "1") (pinfunction "A15_1") (pintype "input"))
    )
    (net (code "93") (name "Net-(U5A-D)") (class "Default")
      (node (ref "U5") (pin "2") (pinfunction "D_2") (pintype "input"))
      (node (ref "U5") (pin "6") (pinfunction "~{Q}_6") (pintype "output"))
    )
    (net (code "94") (name "Net-(U6-OE)") (class "Default")
      (node (ref "J3") (pin "2") (pinfunction "2_2") (pintype "passive"))
      (node (ref "U6") (pin "11") (pinfunction "OE_11") (pintype "input"))
    )
    (net (code "95") (name "PSG_CLK") (class "Default")
      (node (ref "J6") (pin "9") (pinfunction "9_9") (pintype "passive"))
      (node (ref "U2") (pin "22") (pinfunction "CLK_22") (pintype "input"))
      (node (ref "U5") (pin "5") (pinfunction "Q_5") (pintype "output"))
    )
    (net (code "96") (name "RAM-A14") (class "Default")
      (node (ref "U1") (pin "10") (pinfunction "A14_10") (pintype "input"))
      (node (ref "U6") (pin "19") (pinfunction "O1_19") (pintype "output"))
    )
    (net (code "97") (name "SND") (class "Default")
      (node (ref "J6") (pin "21") (pinfunction "21_21") (pintype "passive"))
      (node (ref "SJ4") (pin "1") (pinfunction "1_1") (pintype "passive"))
      (node (ref "XC1") (pin "P$2") (pinfunction "X2_P$2") (pintype "bidirectional"))
    )
    (net (code "98") (name "VCC") (class "Default")
      (node (ref "C1") (pin "2") (pinfunction "2_2") (pintype "passive"))
      (node (ref "C2") (pin "1") (pinfunction "1_1") (pintype "passive"))
      (node (ref "C3") (pin "2") (pinfunction "2_2") (pintype "passive"))
      (node (ref "C4") (pin "2") (pinfunction "2_2") (pintype "passive"))
      (node (ref "C5") (pin "2") (pinfunction "2_2") (pintype "passive"))
      (node (ref "C6") (pin "2") (pinfunction "2_2") (pintype "passive"))
      (node (ref "C7") (pin "2") (pinfunction "2_2") (pintype "passive"))
      (node (ref "C8") (pin "2") (pinfunction "2_2") (pintype "passive"))
      (node (ref "C9") (pin "+") (pinfunction "+_+") (pintype "passive"))
      (node (ref "J3") (pin "1") (pinfunction "1_1") (pintype "passive"))
      (node (ref "J4") (pin "10") (pinfunction "10_10") (pintype "passive"))
      (node (ref "J4") (pin "11") (pinfunction "11_11") (pintype "passive"))
      (node (ref "J5") (pin "1") (pinfunction "1_1") (pintype "passive"))
      (node (ref "J6") (pin "22") (pinfunction "22_22") (pintype "passive"))
      (node (ref "J8") (pin "3") (pinfunction "3_3") (pintype "passive"))
      (node (ref "J9") (pin "3") (pinfunction "3_3") (pintype "passive"))
      (node (ref "JP1") (pin "3") (pinfunction "3_3") (pintype "passive"))
      (node (ref "JP3") (pin "8") (pinfunction "8_8") (pintype "passive"))
      (node (ref "R3") (pin "2") (pinfunction "2_2") (pintype "passive"))
      (node (ref "U2") (pin "25") (pinfunction "A8_25") (pintype "bidirectional"))
      (node (ref "U2") (pin "28") (pinfunction "BC2_28") (pintype "bidirectional"))
      (node (ref "U2") (pin "40") (pinfunction "VCC_40") (pintype "power_in"))
      (node (ref "U3") (pin "28") (pinfunction "VCC_28") (pintype "power_in"))
      (node (ref "U4") (pin "20") (pinfunction "VCC_20") (pintype "power_in"))
      (node (ref "U5") (pin "1") (pinfunction "CLR_1") (pintype "input"))
      (node (ref "U5") (pin "4") (pinfunction "PRE_4") (pintype "input"))
      (node (ref "U6") (pin "20") (pinfunction "VCC_20") (pintype "power_in"))
      (node (ref "U9") (pin "3") (pinfunction "VCC_3") (pintype "power_in"))
      (node (ref "XC1") (pin "P$25") (pinfunction "X25_P$25") (pintype "bidirectional"))
    )
    (net (code "99") (name "unconnected-(JP3-Pad4)") (class "Default")
      (node (ref "JP3") (pin "4") (pinfunction "4_4") (pintype "passive"))
    )
    (net (code "100") (name "unconnected-(U2-TST1-Pad39)") (class "Default")
      (node (ref "U2") (pin "39") (pinfunction "TST1_39") (pintype "bidirectional"))
    )
    (net (code "101") (name "unconnected-(U2-TST2-Pad26)") (class "Default")
      (node (ref "U2") (pin "26") (pinfunction "TST2_26") (pintype "bidirectional"))
    )
    (net (code "102") (name "unconnected-(U5B-CLK-Pad11)") (class "Default")
      (node (ref "U5") (pin "11") (pinfunction "CLK_11") (pintype "input"))
    )
    (net (code "103") (name "unconnected-(U5B-CLR-Pad13)") (class "Default")
      (node (ref "U5") (pin "13") (pinfunction "CLR_13") (pintype "input"))
    )
    (net (code "104") (name "unconnected-(U5B-D-Pad12)") (class "Default")
      (node (ref "U5") (pin "12") (pinfunction "D_12") (pintype "input"))
    )
    (net (code "105") (name "unconnected-(U5B-PRE-Pad10)") (class "Default")
      (node (ref "U5") (pin "10") (pinfunction "PRE_10") (pintype "input"))
    )
    (net (code "106") (name "unconnected-(U5B-Q-Pad9)") (class "Default")
      (node (ref "U5") (pin "9") (pinfunction "Q_9") (pintype "output"))
    )
    (net (code "107") (name "unconnected-(U5B-~{Q}-Pad8)") (class "Default")
      (node (ref "U5") (pin "8") (pinfunction "~{Q}_8") (pintype "output"))
    )
    (net (code "108") (name "unconnected-(U6-O2-Pad18)") (class "Default")
      (node (ref "U6") (pin "18") (pinfunction "O2_18") (pintype "output"))
    )
    (net (code "109") (name "Φ") (class "Default")
      (node (ref "J6") (pin "14") (pinfunction "14_14") (pintype "passive"))
      (node (ref "U5") (pin "3") (pinfunction "CLK_3") (pintype "input"))
      (node (ref "XC1") (pin "P$8") (pinfunction "X8_P$8") (pintype "bidirectional"))
    )
  )
)
